# Old_Shutters_Signal_Interface_-_SiLabs.net
KiCad netlist of a schematic drawn in EAGLE
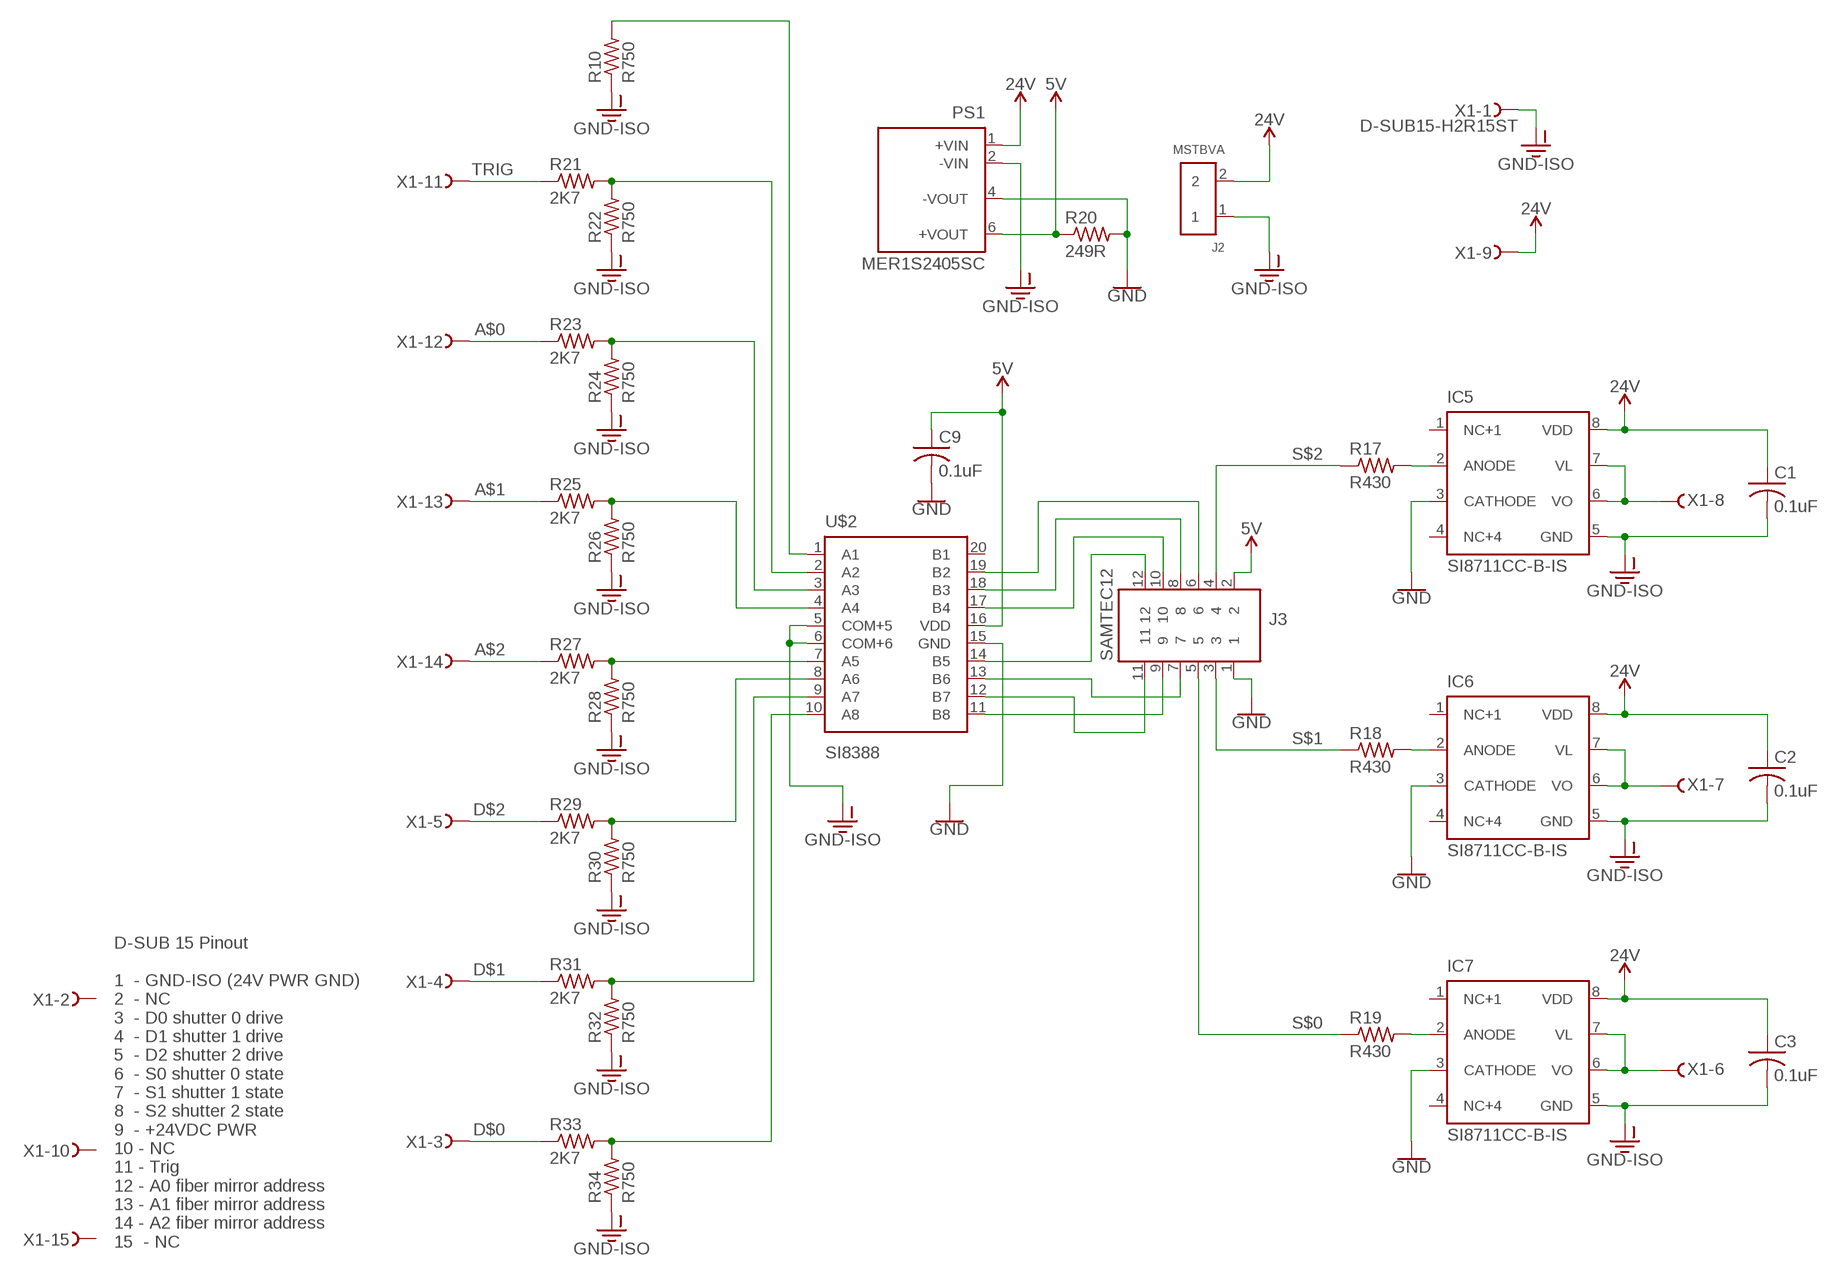
[diagram p0: schematic, sheet 1]

(export (version "E")
  (design (tool "Eeschema 10.0.6"))
  (components
    (comp (ref "C1")
      (value "0.1uF")
      (footprint "eagle-import:C0805")
      (libsource (lib "eagle-import") (part "C-USC0805"))
    )
    (comp (ref "C2")
      (value "0.1uF")
      (footprint "eagle-import:C0805")
      (libsource (lib "eagle-import") (part "C-USC0805"))
    )
    (comp (ref "C3")
      (value "0.1uF")
      (footprint "eagle-import:C0805")
      (libsource (lib "eagle-import") (part "C-USC0805"))
    )
    (comp (ref "C9")
      (value "0.1uF")
      (footprint "eagle-import:C0805")
      (libsource (lib "eagle-import") (part "C-USC0805"))
    )
    (comp (ref "IC5")
      (value "SI8711CC-B-IS")
      (footprint "eagle-import:SO08")
      (libsource (lib "eagle-import") (part "SI8711CC-B-IS"))
    )
    (comp (ref "IC6")
      (value "SI8711CC-B-IS")
      (footprint "eagle-import:SO08")
      (libsource (lib "eagle-import") (part "SI8711CC-B-IS"))
    )
    (comp (ref "IC7")
      (value "SI8711CC-B-IS")
      (footprint "eagle-import:SO08")
      (libsource (lib "eagle-import") (part "SI8711CC-B-IS"))
    )
    (comp (ref "J2")
      (value "MSTBVA")
      (footprint "eagle-import:MSTBVA")
      (libsource (lib "eagle-import") (part "MSTBVA"))
    )
    (comp (ref "J3")
      (value "SAMTEC12")
      (footprint "eagle-import:SAMTEC12")
      (libsource (lib "eagle-import") (part "SAMTEC12"))
    )
    (comp (ref "PS1")
      (value "MER1S2405SC")
      (footprint "eagle-import:MER1")
      (libsource (lib "eagle-import") (part "MER1"))
    )
    (comp (ref "R10")
      (value "R750")
      (footprint "eagle-import:R0805")
      (libsource (lib "eagle-import") (part "R-US_R0805"))
    )
    (comp (ref "R17")
      (value "R430")
      (footprint "eagle-import:R0805")
      (libsource (lib "eagle-import") (part "R-US_R0805"))
    )
    (comp (ref "R18")
      (value "R430")
      (footprint "eagle-import:R0805")
      (libsource (lib "eagle-import") (part "R-US_R0805"))
    )
    (comp (ref "R19")
      (value "R430")
      (footprint "eagle-import:R0805")
      (libsource (lib "eagle-import") (part "R-US_R0805"))
    )
    (comp (ref "R20")
      (value "249R")
      (footprint "eagle-import:R0805")
      (libsource (lib "eagle-import") (part "R-US_R0805"))
    )
    (comp (ref "R21")
      (value "2K7")
      (footprint "eagle-import:R0805")
      (libsource (lib "eagle-import") (part "R-US_R0805"))
    )
    (comp (ref "R22")
      (value "R750")
      (footprint "eagle-import:R0805")
      (libsource (lib "eagle-import") (part "R-US_R0805"))
    )
    (comp (ref "R23")
      (value "2K7")
      (footprint "eagle-import:R0805")
      (libsource (lib "eagle-import") (part "R-US_R0805"))
    )
    (comp (ref "R24")
      (value "R750")
      (footprint "eagle-import:R0805")
      (libsource (lib "eagle-import") (part "R-US_R0805"))
    )
    (comp (ref "R25")
      (value "2K7")
      (footprint "eagle-import:R0805")
      (libsource (lib "eagle-import") (part "R-US_R0805"))
    )
    (comp (ref "R26")
      (value "R750")
      (footprint "eagle-import:R0805")
      (libsource (lib "eagle-import") (part "R-US_R0805"))
    )
    (comp (ref "R27")
      (value "2K7")
      (footprint "eagle-import:R0805")
      (libsource (lib "eagle-import") (part "R-US_R0805"))
    )
    (comp (ref "R28")
      (value "R750")
      (footprint "eagle-import:R0805")
      (libsource (lib "eagle-import") (part "R-US_R0805"))
    )
    (comp (ref "R29")
      (value "2K7")
      (footprint "eagle-import:R0805")
      (libsource (lib "eagle-import") (part "R-US_R0805"))
    )
    (comp (ref "R30")
      (value "R750")
      (footprint "eagle-import:R0805")
      (libsource (lib "eagle-import") (part "R-US_R0805"))
    )
    (comp (ref "R31")
      (value "2K7")
      (footprint "eagle-import:R0805")
      (libsource (lib "eagle-import") (part "R-US_R0805"))
    )
    (comp (ref "R32")
      (value "R750")
      (footprint "eagle-import:R0805")
      (libsource (lib "eagle-import") (part "R-US_R0805"))
    )
    (comp (ref "R33")
      (value "2K7")
      (footprint "eagle-import:R0805")
      (libsource (lib "eagle-import") (part "R-US_R0805"))
    )
    (comp (ref "R34")
      (value "R750")
      (footprint "eagle-import:R0805")
      (libsource (lib "eagle-import") (part "R-US_R0805"))
    )
    (comp (ref "U$2")
      (value "SI8388")
      (footprint "eagle-import:20-QSOP")
      (libsource (lib "eagle-import") (part "SI8388"))
    )
    (comp (ref "X1")
      (value "D-SUB15-H2R15ST")
      (footprint "eagle-import:H2R15ST")
      (libsource (lib "eagle-import") (part "D-SUB15-H2R15ST"))
    )
  )
  (nets
    (net (code "1") (name "/A$0") (class "Default")
      (node (ref "R23") (pin "1") (pinfunction "1_1") (pintype "passive"))
      (node (ref "X1") (pin "12") (pinfunction "F_12") (pintype "passive"))
    )
    (net (code "2") (name "/A$1") (class "Default")
      (node (ref "R25") (pin "1") (pinfunction "1_1") (pintype "passive"))
      (node (ref "X1") (pin "13") (pinfunction "F_13") (pintype "passive"))
    )
    (net (code "3") (name "/A$2") (class "Default")
      (node (ref "R27") (pin "1") (pinfunction "1_1") (pintype "passive"))
      (node (ref "X1") (pin "14") (pinfunction "F_14") (pintype "passive"))
    )
    (net (code "4") (name "/D$0") (class "Default")
      (node (ref "R33") (pin "1") (pinfunction "1_1") (pintype "passive"))
      (node (ref "X1") (pin "3") (pinfunction "F_3") (pintype "passive"))
    )
    (net (code "5") (name "/D$1") (class "Default")
      (node (ref "R31") (pin "1") (pinfunction "1_1") (pintype "passive"))
      (node (ref "X1") (pin "4") (pinfunction "F_4") (pintype "passive"))
    )
    (net (code "6") (name "/D$2") (class "Default")
      (node (ref "R29") (pin "1") (pinfunction "1_1") (pintype "passive"))
      (node (ref "X1") (pin "5") (pinfunction "F_5") (pintype "passive"))
    )
    (net (code "7") (name "/S$0") (class "Default")
      (node (ref "J3") (pin "5") (pinfunction "5_5") (pintype "bidirectional"))
      (node (ref "R19") (pin "1") (pinfunction "1_1") (pintype "passive"))
    )
    (net (code "8") (name "/S$1") (class "Default")
      (node (ref "J3") (pin "3") (pinfunction "3_3") (pintype "bidirectional"))
      (node (ref "R18") (pin "1") (pinfunction "1_1") (pintype "passive"))
    )
    (net (code "9") (name "/S$2") (class "Default")
      (node (ref "J3") (pin "4") (pinfunction "4_4") (pintype "bidirectional"))
      (node (ref "R17") (pin "1") (pinfunction "1_1") (pintype "passive"))
    )
    (net (code "10") (name "/TRIG") (class "Default")
      (node (ref "R21") (pin "1") (pinfunction "1_1") (pintype "passive"))
      (node (ref "X1") (pin "11") (pinfunction "F_11") (pintype "passive"))
    )
    (net (code "11") (name "5V") (class "Default")
      (node (ref "C9") (pin "1") (pinfunction "1_1") (pintype "passive"))
      (node (ref "J3") (pin "2") (pinfunction "2_2") (pintype "bidirectional"))
      (node (ref "PS1") (pin "6") (pinfunction "+VOUT_6") (pintype "power_in"))
      (node (ref "R20") (pin "1") (pinfunction "1_1") (pintype "passive"))
      (node (ref "U$2") (pin "16") (pinfunction "VDD_16") (pintype "bidirectional"))
    )
    (net (code "12") (name "24V") (class "Default")
      (node (ref "C1") (pin "1") (pinfunction "1_1") (pintype "passive"))
      (node (ref "C2") (pin "1") (pinfunction "1_1") (pintype "passive"))
      (node (ref "C3") (pin "1") (pinfunction "1_1") (pintype "passive"))
      (node (ref "IC5") (pin "8") (pinfunction "VDD_8") (pintype "power_in"))
      (node (ref "IC6") (pin "8") (pinfunction "VDD_8") (pintype "power_in"))
      (node (ref "IC7") (pin "8") (pinfunction "VDD_8") (pintype "power_in"))
      (node (ref "J2") (pin "2") (pinfunction "2_2") (pintype "power_in"))
      (node (ref "PS1") (pin "1") (pinfunction "+VIN_1") (pintype "power_in"))
      (node (ref "X1") (pin "9") (pinfunction "F_9") (pintype "passive"))
    )
    (net (code "13") (name "GND") (class "Default")
      (node (ref "C9") (pin "2") (pinfunction "2_2") (pintype "passive"))
      (node (ref "IC5") (pin "3") (pinfunction "CATHODE_3") (pintype "power_in"))
      (node (ref "IC6") (pin "3") (pinfunction "CATHODE_3") (pintype "power_in"))
      (node (ref "IC7") (pin "3") (pinfunction "CATHODE_3") (pintype "power_in"))
      (node (ref "J3") (pin "1") (pinfunction "1_1") (pintype "bidirectional"))
      (node (ref "PS1") (pin "4") (pinfunction "-VOUT_4") (pintype "power_in"))
      (node (ref "R20") (pin "2") (pinfunction "2_2") (pintype "passive"))
      (node (ref "U$2") (pin "15") (pinfunction "GND_15") (pintype "bidirectional"))
    )
    (net (code "14") (name "GND-ISO") (class "Default")
      (node (ref "C1") (pin "2") (pinfunction "2_2") (pintype "passive"))
      (node (ref "C2") (pin "2") (pinfunction "2_2") (pintype "passive"))
      (node (ref "C3") (pin "2") (pinfunction "2_2") (pintype "passive"))
      (node (ref "IC5") (pin "5") (pinfunction "GND_5") (pintype "power_in"))
      (node (ref "IC6") (pin "5") (pinfunction "GND_5") (pintype "power_in"))
      (node (ref "IC7") (pin "5") (pinfunction "GND_5") (pintype "power_in"))
      (node (ref "J2") (pin "1") (pinfunction "1_1") (pintype "power_in"))
      (node (ref "PS1") (pin "2") (pinfunction "-VIN_2") (pintype "power_in"))
      (node (ref "R10") (pin "1") (pinfunction "1_1") (pintype "passive"))
      (node (ref "R22") (pin "1") (pinfunction "1_1") (pintype "passive"))
      (node (ref "R24") (pin "1") (pinfunction "1_1") (pintype "passive"))
      (node (ref "R26") (pin "1") (pinfunction "1_1") (pintype "passive"))
      (node (ref "R28") (pin "1") (pinfunction "1_1") (pintype "passive"))
      (node (ref "R30") (pin "1") (pinfunction "1_1") (pintype "passive"))
      (node (ref "R32") (pin "1") (pinfunction "1_1") (pintype "passive"))
      (node (ref "R34") (pin "1") (pinfunction "1_1") (pintype "passive"))
      (node (ref "U$2") (pin "5") (pinfunction "COM+5_5") (pintype "bidirectional"))
      (node (ref "U$2") (pin "6") (pinfunction "COM+6_6") (pintype "bidirectional"))
      (node (ref "X1") (pin "1") (pinfunction "F_1") (pintype "passive"))
    )
    (net (code "15") (name "Net-(IC5-ANODE)") (class "Default")
      (node (ref "IC5") (pin "2") (pinfunction "ANODE_2") (pintype "input"))
      (node (ref "R17") (pin "2") (pinfunction "2_2") (pintype "passive"))
    )
    (net (code "16") (name "Net-(IC5-VL)") (class "Default")
      (node (ref "IC5") (pin "6") (pinfunction "VO_6") (pintype "open_collector"))
      (node (ref "IC5") (pin "7") (pinfunction "VL_7") (pintype "passive"))
      (node (ref "X1") (pin "8") (pinfunction "F_8") (pintype "passive"))
    )
    (net (code "17") (name "Net-(IC6-ANODE)") (class "Default")
      (node (ref "IC6") (pin "2") (pinfunction "ANODE_2") (pintype "input"))
      (node (ref "R18") (pin "2") (pinfunction "2_2") (pintype "passive"))
    )
    (net (code "18") (name "Net-(IC6-VL)") (class "Default")
      (node (ref "IC6") (pin "6") (pinfunction "VO_6") (pintype "open_collector"))
      (node (ref "IC6") (pin "7") (pinfunction "VL_7") (pintype "passive"))
      (node (ref "X1") (pin "7") (pinfunction "F_7") (pintype "passive"))
    )
    (net (code "19") (name "Net-(IC7-ANODE)") (class "Default")
      (node (ref "IC7") (pin "2") (pinfunction "ANODE_2") (pintype "input"))
      (node (ref "R19") (pin "2") (pinfunction "2_2") (pintype "passive"))
    )
    (net (code "20") (name "Net-(IC7-VL)") (class "Default")
      (node (ref "IC7") (pin "6") (pinfunction "VO_6") (pintype "open_collector"))
      (node (ref "IC7") (pin "7") (pinfunction "VL_7") (pintype "passive"))
      (node (ref "X1") (pin "6") (pinfunction "F_6") (pintype "passive"))
    )
    (net (code "21") (name "Net-(U$2-A1)") (class "Default")
      (node (ref "R10") (pin "2") (pinfunction "2_2") (pintype "passive"))
      (node (ref "U$2") (pin "1") (pinfunction "A1_1") (pintype "bidirectional"))
    )
    (net (code "22") (name "Net-(U$2-A2)") (class "Default")
      (node (ref "R21") (pin "2") (pinfunction "2_2") (pintype "passive"))
      (node (ref "R22") (pin "2") (pinfunction "2_2") (pintype "passive"))
      (node (ref "U$2") (pin "2") (pinfunction "A2_2") (pintype "bidirectional"))
    )
    (net (code "23") (name "Net-(U$2-A3)") (class "Default")
      (node (ref "R23") (pin "2") (pinfunction "2_2") (pintype "passive"))
      (node (ref "R24") (pin "2") (pinfunction "2_2") (pintype "passive"))
      (node (ref "U$2") (pin "3") (pinfunction "A3_3") (pintype "bidirectional"))
    )
    (net (code "24") (name "Net-(U$2-A4)") (class "Default")
      (node (ref "R25") (pin "2") (pinfunction "2_2") (pintype "passive"))
      (node (ref "R26") (pin "2") (pinfunction "2_2") (pintype "passive"))
      (node (ref "U$2") (pin "4") (pinfunction "A4_4") (pintype "bidirectional"))
    )
    (net (code "25") (name "Net-(U$2-A5)") (class "Default")
      (node (ref "R27") (pin "2") (pinfunction "2_2") (pintype "passive"))
      (node (ref "R28") (pin "2") (pinfunction "2_2") (pintype "passive"))
      (node (ref "U$2") (pin "7") (pinfunction "A5_7") (pintype "bidirectional"))
    )
    (net (code "26") (name "Net-(U$2-A6)") (class "Default")
      (node (ref "R29") (pin "2") (pinfunction "2_2") (pintype "passive"))
      (node (ref "R30") (pin "2") (pinfunction "2_2") (pintype "passive"))
      (node (ref "U$2") (pin "8") (pinfunction "A6_8") (pintype "bidirectional"))
    )
    (net (code "27") (name "Net-(U$2-A7)") (class "Default")
      (node (ref "R31") (pin "2") (pinfunction "2_2") (pintype "passive"))
      (node (ref "R32") (pin "2") (pinfunction "2_2") (pintype "passive"))
      (node (ref "U$2") (pin "9") (pinfunction "A7_9") (pintype "bidirectional"))
    )
    (net (code "28") (name "Net-(U$2-A8)") (class "Default")
      (node (ref "R33") (pin "2") (pinfunction "2_2") (pintype "passive"))
      (node (ref "R34") (pin "2") (pinfunction "2_2") (pintype "passive"))
      (node (ref "U$2") (pin "10") (pinfunction "A8_10") (pintype "bidirectional"))
    )
    (net (code "29") (name "Net-(U$2-B2)") (class "Default")
      (node (ref "J3") (pin "6") (pinfunction "6_6") (pintype "bidirectional"))
      (node (ref "U$2") (pin "19") (pinfunction "B2_19") (pintype "bidirectional"))
    )
    (net (code "30") (name "Net-(U$2-B3)") (class "Default")
      (node (ref "J3") (pin "8") (pinfunction "8_8") (pintype "bidirectional"))
      (node (ref "U$2") (pin "18") (pinfunction "B3_18") (pintype "bidirectional"))
    )
    (net (code "31") (name "Net-(U$2-B4)") (class "Default")
      (node (ref "J3") (pin "10") (pinfunction "10_10") (pintype "bidirectional"))
      (node (ref "U$2") (pin "17") (pinfunction "B4_17") (pintype "bidirectional"))
    )
    (net (code "32") (name "Net-(U$2-B5)") (class "Default")
      (node (ref "J3") (pin "12") (pinfunction "12_12") (pintype "bidirectional"))
      (node (ref "U$2") (pin "14") (pinfunction "B5_14") (pintype "bidirectional"))
    )
    (net (code "33") (name "Net-(U$2-B6)") (class "Default")
      (node (ref "J3") (pin "7") (pinfunction "7_7") (pintype "bidirectional"))
      (node (ref "U$2") (pin "13") (pinfunction "B6_13") (pintype "bidirectional"))
    )
    (net (code "34") (name "Net-(U$2-B7)") (class "Default")
      (node (ref "J3") (pin "11") (pinfunction "11_11") (pintype "bidirectional"))
      (node (ref "U$2") (pin "12") (pinfunction "B7_12") (pintype "bidirectional"))
    )
    (net (code "35") (name "Net-(U$2-B8)") (class "Default")
      (node (ref "J3") (pin "9") (pinfunction "9_9") (pintype "bidirectional"))
      (node (ref "U$2") (pin "11") (pinfunction "B8_11") (pintype "bidirectional"))
    )
    (net (code "36") (name "unconnected-(IC5-NC+1-Pad1)") (class "Default")
      (node (ref "IC5") (pin "1") (pinfunction "NC+1_1") (pintype "no_connect"))
    )
    (net (code "37") (name "unconnected-(IC5-NC+4-Pad4)") (class "Default")
      (node (ref "IC5") (pin "4") (pinfunction "NC+4_4") (pintype "no_connect"))
    )
    (net (code "38") (name "unconnected-(IC6-NC+1-Pad1)") (class "Default")
      (node (ref "IC6") (pin "1") (pinfunction "NC+1_1") (pintype "no_connect"))
    )
    (net (code "39") (name "unconnected-(IC6-NC+4-Pad4)") (class "Default")
      (node (ref "IC6") (pin "4") (pinfunction "NC+4_4") (pintype "no_connect"))
    )
    (net (code "40") (name "unconnected-(IC7-NC+1-Pad1)") (class "Default")
      (node (ref "IC7") (pin "1") (pinfunction "NC+1_1") (pintype "no_connect"))
    )
    (net (code "41") (name "unconnected-(IC7-NC+4-Pad4)") (class "Default")
      (node (ref "IC7") (pin "4") (pinfunction "NC+4_4") (pintype "no_connect"))
    )
    (net (code "42") (name "unconnected-(U$2-B1-Pad20)") (class "Default")
      (node (ref "U$2") (pin "20") (pinfunction "B1_20") (pintype "bidirectional"))
    )
    (net (code "43") (name "unconnected-(X1B-F-Pad10)") (class "Default")
      (node (ref "X1") (pin "10") (pinfunction "F_10") (pintype "passive"))
    )
    (net (code "44") (name "unconnected-(X1G-F-Pad15)") (class "Default")
      (node (ref "X1") (pin "15") (pinfunction "F_15") (pintype "passive"))
    )
    (net (code "45") (name "unconnected-(X1H-F-Pad2)") (class "Default")
      (node (ref "X1") (pin "2") (pinfunction "F_2") (pintype "passive"))
    )
  )
)
